# b.net
KiCad netlist of a schematic drawn in EAGLE
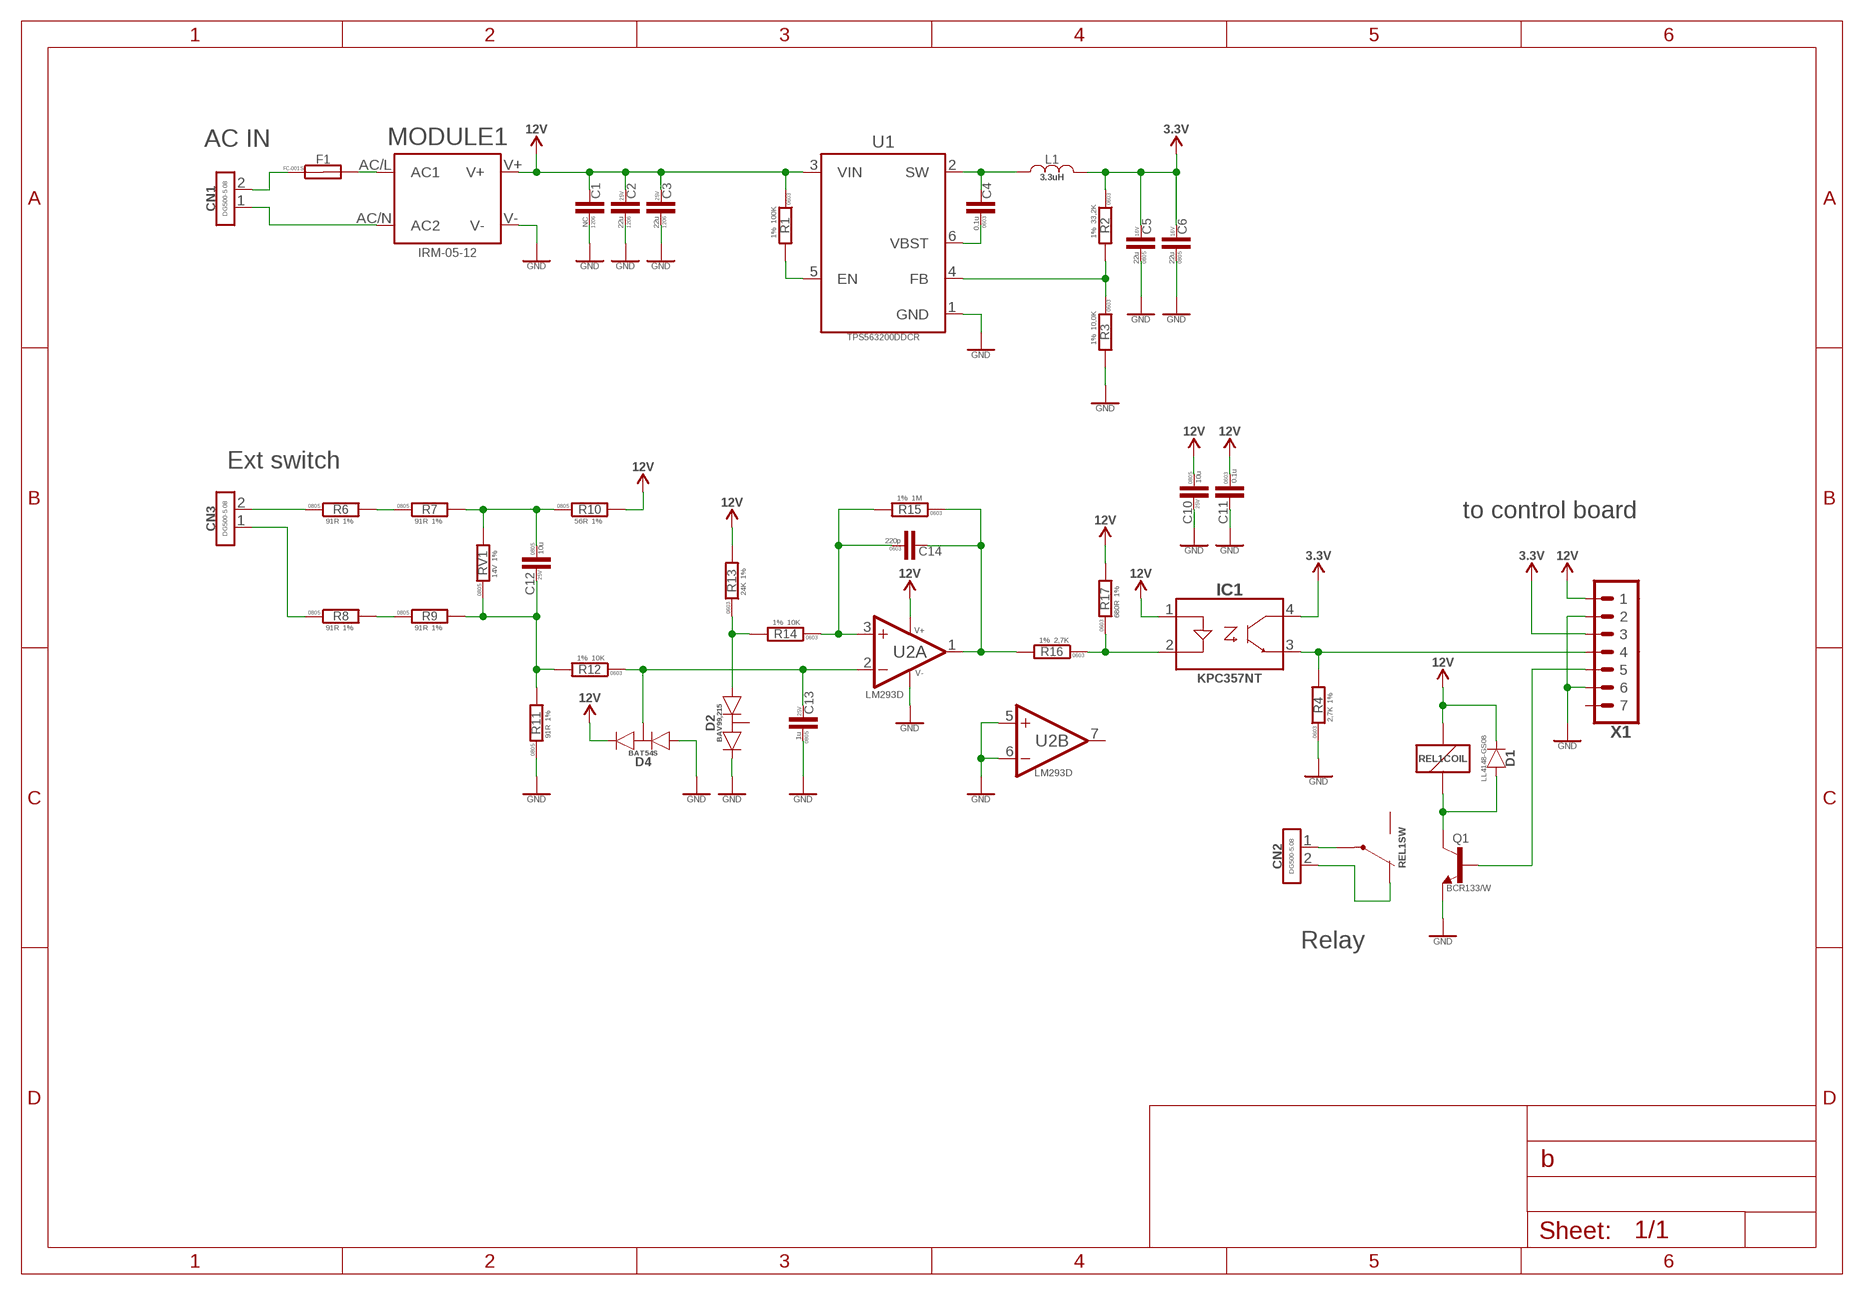
[diagram p0: schematic, sheet 1]

(export (version "E")
  (design (tool "Eeschema 10.0.6"))
  (components
    (comp (ref "C1")
      (value "NC")
      (footprint "eagle-import:C1206")
      (fields (field (name "PACKAGE") "1206"))
      (libsource (lib "eagle-import") (part "C-1206"))
    )
    (comp (ref "C2")
      (value "22u")
      (footprint "eagle-import:C1206")
      (fields (field (name "PACKAGE") "1206") (field (name "VOLTAGE") "25V"))
      (libsource (lib "eagle-import") (part "C-1206"))
    )
    (comp (ref "C3")
      (value "22u")
      (footprint "eagle-import:C1206")
      (fields (field (name "PACKAGE") "1206") (field (name "VOLTAGE") "25V"))
      (libsource (lib "eagle-import") (part "C-1206"))
    )
    (comp (ref "C4")
      (value "0.1u")
      (footprint "eagle-import:C0603")
      (fields (field (name "PACKAGE") "0603"))
      (libsource (lib "eagle-import") (part "C-0603"))
    )
    (comp (ref "C5")
      (value "22u")
      (footprint "eagle-import:C0805")
      (fields (field (name "PACKAGE") "0805") (field (name "VOLTAGE") "16V"))
      (libsource (lib "eagle-import") (part "C-0805"))
    )
    (comp (ref "C6")
      (value "22u")
      (footprint "eagle-import:C0805")
      (fields (field (name "PACKAGE") "0805") (field (name "VOLTAGE") "16V"))
      (libsource (lib "eagle-import") (part "C-0805"))
    )
    (comp (ref "C10")
      (value "10u")
      (footprint "eagle-import:C0805")
      (fields (field (name "PACKAGE") "0805") (field (name "VOLTAGE") "25V"))
      (libsource (lib "eagle-import") (part "C-0805"))
    )
    (comp (ref "C11")
      (value "0.1u")
      (footprint "eagle-import:C0603")
      (fields (field (name "PACKAGE") "0603"))
      (libsource (lib "eagle-import") (part "C-0603"))
    )
    (comp (ref "C12")
      (value "10u")
      (footprint "eagle-import:C0805")
      (fields (field (name "PACKAGE") "0805") (field (name "VOLTAGE") "25V"))
      (libsource (lib "eagle-import") (part "C-0805"))
    )
    (comp (ref "C13")
      (value "1u")
      (footprint "eagle-import:C0805")
      (fields (field (name "PACKAGE") "0805") (field (name "VOLTAGE") "25V"))
      (libsource (lib "eagle-import") (part "C-0805"))
    )
    (comp (ref "C14")
      (value "220p")
      (footprint "eagle-import:C0603")
      (fields (field (name "PACKAGE") "0603"))
      (libsource (lib "eagle-import") (part "C-0603"))
    )
    (comp (ref "CN1")
      (value "DG508V-2P")
      (footprint "eagle-import:DG500-5.08-02P")
      (fields (field (name "TYPE") "DG500-5.08") (field (name "MANF") "Degson Electronics"))
      (libsource (lib "eagle-import") (part "CON-2P-DG500-5.08"))
    )
    (comp (ref "CN2")
      (value "CON-2P-DG500-5.08")
      (footprint "eagle-import:DG500-5.08-02P")
      (fields (field (name "TYPE") "DG500-5.08") (field (name "MANF") "Degson Electronics"))
      (libsource (lib "eagle-import") (part "CON-2P-DG500-5.08"))
    )
    (comp (ref "CN3")
      (value "DG508V-2P")
      (footprint "eagle-import:DG500-5.08-02P")
      (fields (field (name "TYPE") "DG500-5.08") (field (name "MANF") "Degson Electronics"))
      (libsource (lib "eagle-import") (part "CON-2P-DG500-5.08"))
    )
    (comp (ref "D1")
      (value "LL4148")
      (footprint "eagle-import:LL-34")
      (fields (field (name "MANF#") "LL4148-GS08") (field (name "MANF") "VISHAY INTERTECHNOLOGY INC"))
      (libsource (lib "eagle-import") (part "LL4148"))
    )
    (comp (ref "D2")
      (value "BAV99-SOT23")
      (footprint "eagle-import:SOT23")
      (fields (field (name "MANF#") "BAV99,215") (field (name "MANF") "NEXPERIA"))
      (libsource (lib "eagle-import") (part "BAV99-SOT23"))
    )
    (comp (ref "D4")
      (value "BAT54S-SOT23")
      (footprint "eagle-import:SOT23")
      (fields (field (name "MANF#") "BAT54S") (field (name "MANF") "NEXPERIA"))
      (libsource (lib "eagle-import") (part "BAT54S-SOT23"))
    )
    (comp (ref "F1")
      (value "2A")
      (footprint "eagle-import:FC-001S")
      (fields (field (name "PACKAGE") "FC-001S"))
      (libsource (lib "eagle-import") (part "FUSE-FC-001S"))
    )
    (comp (ref "IC1")
      (value "KPC357NT-SOP-4")
      (footprint "eagle-import:-SOP-4")
      (fields (field (name "MANF#") "KPC357NT") (field (name "MANF") "COSMO"))
      (libsource (lib "eagle-import") (part "KPC357NT-SOP-4"))
    )
    (comp (ref "L1")
      (value "3.3uH")
      (footprint "eagle-import:LSMD_05020")
      (fields (field (name "MANF") "Chilisin"))
      (libsource (lib "eagle-import") (part "3.3µH-0520"))
    )
    (comp (ref "MODULE1")
      (value "IRM-05-12")
      (footprint "eagle-import:IRM-05")
      (fields (field (name "MANF#") "IRM-05-12") (field (name "MANF") "Meanwell"))
      (libsource (lib "eagle-import") (part "IRM-05-12"))
    )
    (comp (ref "Q1")
      (value "BCR133")
      (footprint "eagle-import:SOT23B-3")
      (fields (field (name "MANF#") "BCR133/W") (field (name "MANF") "INFINEON TECHNOLOGIES AG."))
      (libsource (lib "eagle-import") (part "BCR133"))
    )
    (comp (ref "R1")
      (value "100K")
      (footprint "eagle-import:R0603")
      (fields (field (name "PACKAGE") "0603") (field (name "TOLERANCE") "1%"))
      (libsource (lib "eagle-import") (part "R-0603-1%"))
    )
    (comp (ref "R2")
      (value "33,2K")
      (footprint "eagle-import:R0603")
      (fields (field (name "PACKAGE") "0603") (field (name "TOLERANCE") "1%"))
      (libsource (lib "eagle-import") (part "R-0603-1%"))
    )
    (comp (ref "R3")
      (value "10,0K")
      (footprint "eagle-import:R0603")
      (fields (field (name "PACKAGE") "0603") (field (name "TOLERANCE") "1%"))
      (libsource (lib "eagle-import") (part "R-0603-1%"))
    )
    (comp (ref "R4")
      (value "2,7K")
      (footprint "eagle-import:R0603")
      (fields (field (name "PACKAGE") "0603") (field (name "TOLERANCE") "1%"))
      (libsource (lib "eagle-import") (part "R-0603-1%"))
    )
    (comp (ref "R6")
      (value "91R")
      (footprint "eagle-import:R0805")
      (fields (field (name "PACKAGE") "0805") (field (name "TOLERANCE") "1%"))
      (libsource (lib "eagle-import") (part "R-0805-1%"))
    )
    (comp (ref "R7")
      (value "91R")
      (footprint "eagle-import:R0805")
      (fields (field (name "PACKAGE") "0805") (field (name "TOLERANCE") "1%"))
      (libsource (lib "eagle-import") (part "R-0805-1%"))
    )
    (comp (ref "R8")
      (value "91R")
      (footprint "eagle-import:R0805")
      (fields (field (name "PACKAGE") "0805") (field (name "TOLERANCE") "1%"))
      (libsource (lib "eagle-import") (part "R-0805-1%"))
    )
    (comp (ref "R9")
      (value "91R")
      (footprint "eagle-import:R0805")
      (fields (field (name "PACKAGE") "0805") (field (name "TOLERANCE") "1%"))
      (libsource (lib "eagle-import") (part "R-0805-1%"))
    )
    (comp (ref "R10")
      (value "56R")
      (footprint "eagle-import:R0805")
      (fields (field (name "PACKAGE") "0805") (field (name "TOLERANCE") "1%"))
      (libsource (lib "eagle-import") (part "R-0805-1%"))
    )
    (comp (ref "R11")
      (value "91R")
      (footprint "eagle-import:R0805")
      (fields (field (name "PACKAGE") "0805") (field (name "TOLERANCE") "1%"))
      (libsource (lib "eagle-import") (part "R-0805-1%"))
    )
    (comp (ref "R12")
      (value "10K")
      (footprint "eagle-import:R0603")
      (fields (field (name "PACKAGE") "0603") (field (name "TOLERANCE") "1%"))
      (libsource (lib "eagle-import") (part "R-0603-1%"))
    )
    (comp (ref "R13")
      (value "24K")
      (footprint "eagle-import:R0603")
      (fields (field (name "PACKAGE") "0603") (field (name "TOLERANCE") "1%"))
      (libsource (lib "eagle-import") (part "R-0603-1%"))
    )
    (comp (ref "R14")
      (value "10K")
      (footprint "eagle-import:R0603")
      (fields (field (name "PACKAGE") "0603") (field (name "TOLERANCE") "1%"))
      (libsource (lib "eagle-import") (part "R-0603-1%"))
    )
    (comp (ref "R15")
      (value "1M")
      (footprint "eagle-import:R0603")
      (fields (field (name "PACKAGE") "0603") (field (name "TOLERANCE") "1%"))
      (libsource (lib "eagle-import") (part "R-0603-1%"))
    )
    (comp (ref "R16")
      (value "2,7K")
      (footprint "eagle-import:R0603")
      (fields (field (name "PACKAGE") "0603") (field (name "TOLERANCE") "1%"))
      (libsource (lib "eagle-import") (part "R-0603-1%"))
    )
    (comp (ref "R17")
      (value "680R")
      (footprint "eagle-import:R0603")
      (fields (field (name "PACKAGE") "0603") (field (name "TOLERANCE") "1%"))
      (libsource (lib "eagle-import") (part "R-0603-1%"))
    )
    (comp (ref "REL1")
      (value "RELAY_SPDTHJR-3FF-SH")
      (footprint "eagle-import:HJR-3FF-12VDC-S-Z")
      (fields (field (name "MANF") "Tianbo"))
      (libsource (lib "eagle-import") (part "RELAY_SPDTHJR-3FF-SH"))
    )
    (comp (ref "RV1")
      (value "14V")
      (footprint "eagle-import:R0805")
      (fields (field (name "PACKAGE") "0805") (field (name "TOLERANCE") "1%"))
      (libsource (lib "eagle-import") (part "R-0805-1%"))
    )
    (comp (ref "U1")
      (value "TPS563200")
      (footprint "eagle-import:SOT23-6")
      (fields (field (name "MANF#") "TPS563200DDCR") (field (name "MANF") "Texas Instruments"))
      (libsource (lib "eagle-import") (part "TPS563200"))
    )
    (comp (ref "U2")
      (value "LM293D")
      (footprint "eagle-import:SOIC8")
      (fields (field (name "MANF#") "LM293D") (field (name "MANF") "STMicroelectronics"))
      (libsource (lib "eagle-import") (part "LM293D-SO8"))
    )
    (comp (ref "X1")
      (value "PINHEAD_1X07-2.54")
      (footprint "eagle-import:1X07-PTH-2.54")
      (libsource (lib "eagle-import") (part "PINHEAD_1X07-2.54"))
    )
  )
  (nets
    (net (code "1") (name "3.3V") (class "Default")
      (node (ref "C5") (pin "2") (pinfunction "2_2") (pintype "passive"))
      (node (ref "C6") (pin "2") (pinfunction "2_2") (pintype "passive"))
      (node (ref "IC1") (pin "4") (pinfunction "COLLECTOR_4") (pintype "bidirectional"))
      (node (ref "L1") (pin "2") (pinfunction "2_2") (pintype "bidirectional"))
      (node (ref "R2") (pin "1") (pinfunction "1_1") (pintype "passive"))
      (node (ref "X1") (pin "3") (pinfunction "3_3") (pintype "passive"))
    )
    (net (code "2") (name "12V") (class "Default")
      (node (ref "C1") (pin "P$2") (pinfunction "2_P$2") (pintype "passive"))
      (node (ref "C10") (pin "1") (pinfunction "1_1") (pintype "passive"))
      (node (ref "C11") (pin "1") (pinfunction "1_1") (pintype "passive"))
      (node (ref "C2") (pin "P$2") (pinfunction "2_P$2") (pintype "passive"))
      (node (ref "C3") (pin "P$2") (pinfunction "2_P$2") (pintype "passive"))
      (node (ref "D1") (pin "C") (pinfunction "C_C") (pintype "passive"))
      (node (ref "D4") (pin "2") (pinfunction "C_2") (pintype "passive"))
      (node (ref "IC1") (pin "1") (pinfunction "A_1") (pintype "bidirectional"))
      (node (ref "MODULE1") (pin "V+") (pinfunction "V+_V+") (pintype "bidirectional"))
      (node (ref "R1") (pin "1") (pinfunction "1_1") (pintype "passive"))
      (node (ref "R10") (pin "2") (pinfunction "2_2") (pintype "passive"))
      (node (ref "R13") (pin "2") (pinfunction "2_2") (pintype "passive"))
      (node (ref "R17") (pin "2") (pinfunction "2_2") (pintype "passive"))
      (node (ref "REL1") (pin "5") (pinfunction "2_5") (pintype "passive"))
      (node (ref "U1") (pin "3") (pinfunction "VIN_3") (pintype "bidirectional"))
      (node (ref "U2") (pin "8") (pinfunction "V+_8") (pintype "power_in"))
      (node (ref "X1") (pin "1") (pinfunction "1_1") (pintype "passive"))
    )
    (net (code "3") (name "GND") (class "Default")
      (node (ref "C1") (pin "P$1") (pinfunction "1_P$1") (pintype "passive"))
      (node (ref "C10") (pin "2") (pinfunction "2_2") (pintype "passive"))
      (node (ref "C11") (pin "2") (pinfunction "2_2") (pintype "passive"))
      (node (ref "C13") (pin "1") (pinfunction "1_1") (pintype "passive"))
      (node (ref "C2") (pin "P$1") (pinfunction "1_P$1") (pintype "passive"))
      (node (ref "C3") (pin "P$1") (pinfunction "1_P$1") (pintype "passive"))
      (node (ref "C5") (pin "1") (pinfunction "1_1") (pintype "passive"))
      (node (ref "C6") (pin "1") (pinfunction "1_1") (pintype "passive"))
      (node (ref "D2") (pin "2") (pinfunction "C_2") (pintype "passive"))
      (node (ref "D4") (pin "1") (pinfunction "A_1") (pintype "passive"))
      (node (ref "MODULE1") (pin "V-") (pinfunction "V-_V-") (pintype "bidirectional"))
      (node (ref "Q1") (pin "2") (pinfunction "E_2") (pintype "passive"))
      (node (ref "R11") (pin "1") (pinfunction "1_1") (pintype "passive"))
      (node (ref "R3") (pin "2") (pinfunction "2_2") (pintype "passive"))
      (node (ref "R4") (pin "1") (pinfunction "1_1") (pintype "passive"))
      (node (ref "U1") (pin "1") (pinfunction "GND_1") (pintype "bidirectional"))
      (node (ref "U2") (pin "4") (pinfunction "V-_4") (pintype "power_in"))
      (node (ref "U2") (pin "5") (pinfunction "IN+_5") (pintype "input"))
      (node (ref "U2") (pin "6") (pinfunction "IN-_6") (pintype "input"))
      (node (ref "X1") (pin "2") (pinfunction "2_2") (pintype "passive"))
      (node (ref "X1") (pin "6") (pinfunction "6_6") (pintype "passive"))
    )
    (net (code "4") (name "Net-(C12-Pad1)") (class "Default")
      (node (ref "C12") (pin "1") (pinfunction "1_1") (pintype "passive"))
      (node (ref "R10") (pin "1") (pinfunction "1_1") (pintype "passive"))
      (node (ref "R7") (pin "2") (pinfunction "2_2") (pintype "passive"))
      (node (ref "RV1") (pin "2") (pinfunction "2_2") (pintype "passive"))
    )
    (net (code "5") (name "Net-(C12-Pad2)") (class "Default")
      (node (ref "C12") (pin "2") (pinfunction "2_2") (pintype "passive"))
      (node (ref "R11") (pin "2") (pinfunction "2_2") (pintype "passive"))
      (node (ref "R12") (pin "2") (pinfunction "2_2") (pintype "passive"))
      (node (ref "R9") (pin "2") (pinfunction "2_2") (pintype "passive"))
      (node (ref "RV1") (pin "1") (pinfunction "1_1") (pintype "passive"))
    )
    (net (code "6") (name "Net-(CN1-Pad2)") (class "Default")
      (node (ref "CN1") (pin "2") (pinfunction "2_2") (pintype "bidirectional"))
      (node (ref "F1") (pin "1-1") (pinfunction "1_1-1") (pintype "passive"))
      (node (ref "F1") (pin "1-2") (pinfunction "1_1-2") (pintype "passive"))
    )
    (net (code "7") (name "Net-(CN3-Pad1)") (class "Default")
      (node (ref "CN3") (pin "1") (pinfunction "1_1") (pintype "bidirectional"))
      (node (ref "R8") (pin "1") (pinfunction "1_1") (pintype "passive"))
    )
    (net (code "8") (name "Net-(CN3-Pad2)") (class "Default")
      (node (ref "CN3") (pin "2") (pinfunction "2_2") (pintype "bidirectional"))
      (node (ref "R6") (pin "1") (pinfunction "1_1") (pintype "passive"))
    )
    (net (code "9") (name "Net-(D2-A)") (class "Default")
      (node (ref "D2") (pin "1") (pinfunction "A_1") (pintype "passive"))
      (node (ref "R13") (pin "1") (pinfunction "1_1") (pintype "passive"))
      (node (ref "R14") (pin "2") (pinfunction "2_2") (pintype "passive"))
    )
    (net (code "10") (name "Net-(D4-COMMON)") (class "Default")
      (node (ref "C13") (pin "2") (pinfunction "2_2") (pintype "passive"))
      (node (ref "D4") (pin "3") (pinfunction "COMMON_3") (pintype "bidirectional"))
      (node (ref "R12") (pin "1") (pinfunction "1_1") (pintype "passive"))
      (node (ref "U2") (pin "2") (pinfunction "IN-_2") (pintype "input"))
    )
    (net (code "11") (name "Net-(IC1-C)") (class "Default")
      (node (ref "IC1") (pin "2") (pinfunction "C_2") (pintype "bidirectional"))
      (node (ref "R16") (pin "1") (pinfunction "1_1") (pintype "passive"))
      (node (ref "R17") (pin "1") (pinfunction "1_1") (pintype "passive"))
    )
    (net (code "12") (name "Net-(IC1-EMITTER)") (class "Default")
      (node (ref "IC1") (pin "3") (pinfunction "EMITTER_3") (pintype "bidirectional"))
      (node (ref "R4") (pin "2") (pinfunction "2_2") (pintype "passive"))
      (node (ref "X1") (pin "4") (pinfunction "4_4") (pintype "passive"))
    )
    (net (code "13") (name "Net-(MODULE1-AC1)") (class "Default")
      (node (ref "F1") (pin "2-1") (pinfunction "2_2-1") (pintype "passive"))
      (node (ref "F1") (pin "2-2") (pinfunction "2_2-2") (pintype "passive"))
      (node (ref "MODULE1") (pin "AC/L") (pinfunction "AC1_AC/L") (pintype "bidirectional"))
    )
    (net (code "14") (name "Net-(MODULE1-AC2)") (class "Default")
      (node (ref "CN1") (pin "1") (pinfunction "1_1") (pintype "bidirectional"))
      (node (ref "MODULE1") (pin "AC/N") (pinfunction "AC2_AC/N") (pintype "bidirectional"))
    )
    (net (code "15") (name "Net-(Q1-B)") (class "Default")
      (node (ref "Q1") (pin "1") (pinfunction "B_1") (pintype "passive"))
      (node (ref "X1") (pin "5") (pinfunction "5_5") (pintype "passive"))
    )
    (net (code "16") (name "Net-(Q1-C)") (class "Default")
      (node (ref "D1") (pin "A") (pinfunction "A_A") (pintype "passive"))
      (node (ref "Q1") (pin "3") (pinfunction "C_3") (pintype "passive"))
      (node (ref "REL1") (pin "2") (pinfunction "1_2") (pintype "passive"))
    )
    (net (code "17") (name "Net-(R6-Pad2)") (class "Default")
      (node (ref "R6") (pin "2") (pinfunction "2_2") (pintype "passive"))
      (node (ref "R7") (pin "1") (pinfunction "1_1") (pintype "passive"))
    )
    (net (code "18") (name "Net-(R8-Pad2)") (class "Default")
      (node (ref "R8") (pin "2") (pinfunction "2_2") (pintype "passive"))
      (node (ref "R9") (pin "1") (pinfunction "1_1") (pintype "passive"))
    )
    (net (code "19") (name "Net-(REL1B-COM)") (class "Default")
      (node (ref "CN2") (pin "1") (pinfunction "1_1") (pintype "bidirectional"))
      (node (ref "REL1") (pin "1") (pinfunction "COM_1") (pintype "passive"))
    )
    (net (code "20") (name "Net-(REL1B-NC)") (class "Default")
      (node (ref "CN2") (pin "2") (pinfunction "2_2") (pintype "bidirectional"))
      (node (ref "REL1") (pin "4") (pinfunction "NC_4") (pintype "passive"))
    )
    (net (code "21") (name "Net-(U1-EN)") (class "Default")
      (node (ref "R1") (pin "2") (pinfunction "2_2") (pintype "passive"))
      (node (ref "U1") (pin "5") (pinfunction "EN_5") (pintype "bidirectional"))
    )
    (net (code "22") (name "Net-(U1-FB)") (class "Default")
      (node (ref "R2") (pin "2") (pinfunction "2_2") (pintype "passive"))
      (node (ref "R3") (pin "1") (pinfunction "1_1") (pintype "passive"))
      (node (ref "U1") (pin "4") (pinfunction "FB_4") (pintype "bidirectional"))
    )
    (net (code "23") (name "Net-(U1-SW)") (class "Default")
      (node (ref "C4") (pin "2") (pinfunction "2_2") (pintype "passive"))
      (node (ref "L1") (pin "1") (pinfunction "1_1") (pintype "bidirectional"))
      (node (ref "U1") (pin "2") (pinfunction "SW_2") (pintype "bidirectional"))
    )
    (net (code "24") (name "Net-(U1-VBST)") (class "Default")
      (node (ref "C4") (pin "1") (pinfunction "1_1") (pintype "passive"))
      (node (ref "U1") (pin "6") (pinfunction "VBST_6") (pintype "bidirectional"))
    )
    (net (code "25") (name "Net-(U2A-IN+)") (class "Default")
      (node (ref "C14") (pin "1") (pinfunction "1_1") (pintype "passive"))
      (node (ref "R14") (pin "1") (pinfunction "1_1") (pintype "passive"))
      (node (ref "R15") (pin "2") (pinfunction "2_2") (pintype "passive"))
      (node (ref "U2") (pin "3") (pinfunction "IN+_3") (pintype "input"))
    )
    (net (code "26") (name "Net-(U2A-OUT)") (class "Default")
      (node (ref "C14") (pin "2") (pinfunction "2_2") (pintype "passive"))
      (node (ref "R15") (pin "1") (pinfunction "1_1") (pintype "passive"))
      (node (ref "R16") (pin "2") (pinfunction "2_2") (pintype "passive"))
      (node (ref "U2") (pin "1") (pinfunction "OUT_1") (pintype "output"))
    )
    (net (code "27") (name "unconnected-(D2-COMMON-Pad3)") (class "Default")
      (node (ref "D2") (pin "3") (pinfunction "COMMON_3") (pintype "bidirectional"))
    )
    (net (code "28") (name "unconnected-(REL1B-NO-Pad3)") (class "Default")
      (node (ref "REL1") (pin "3") (pinfunction "NO_3") (pintype "passive"))
    )
    (net (code "29") (name "unconnected-(U2B-OUT-Pad7)") (class "Default")
      (node (ref "U2") (pin "7") (pinfunction "OUT_7") (pintype "output"))
    )
    (net (code "30") (name "unconnected-(X1-Pad7)") (class "Default")
      (node (ref "X1") (pin "7") (pinfunction "7_7") (pintype "passive"))
    )
  )
)
